# led_matrix.net
KiCad netlist of a schematic drawn in Altium Designer
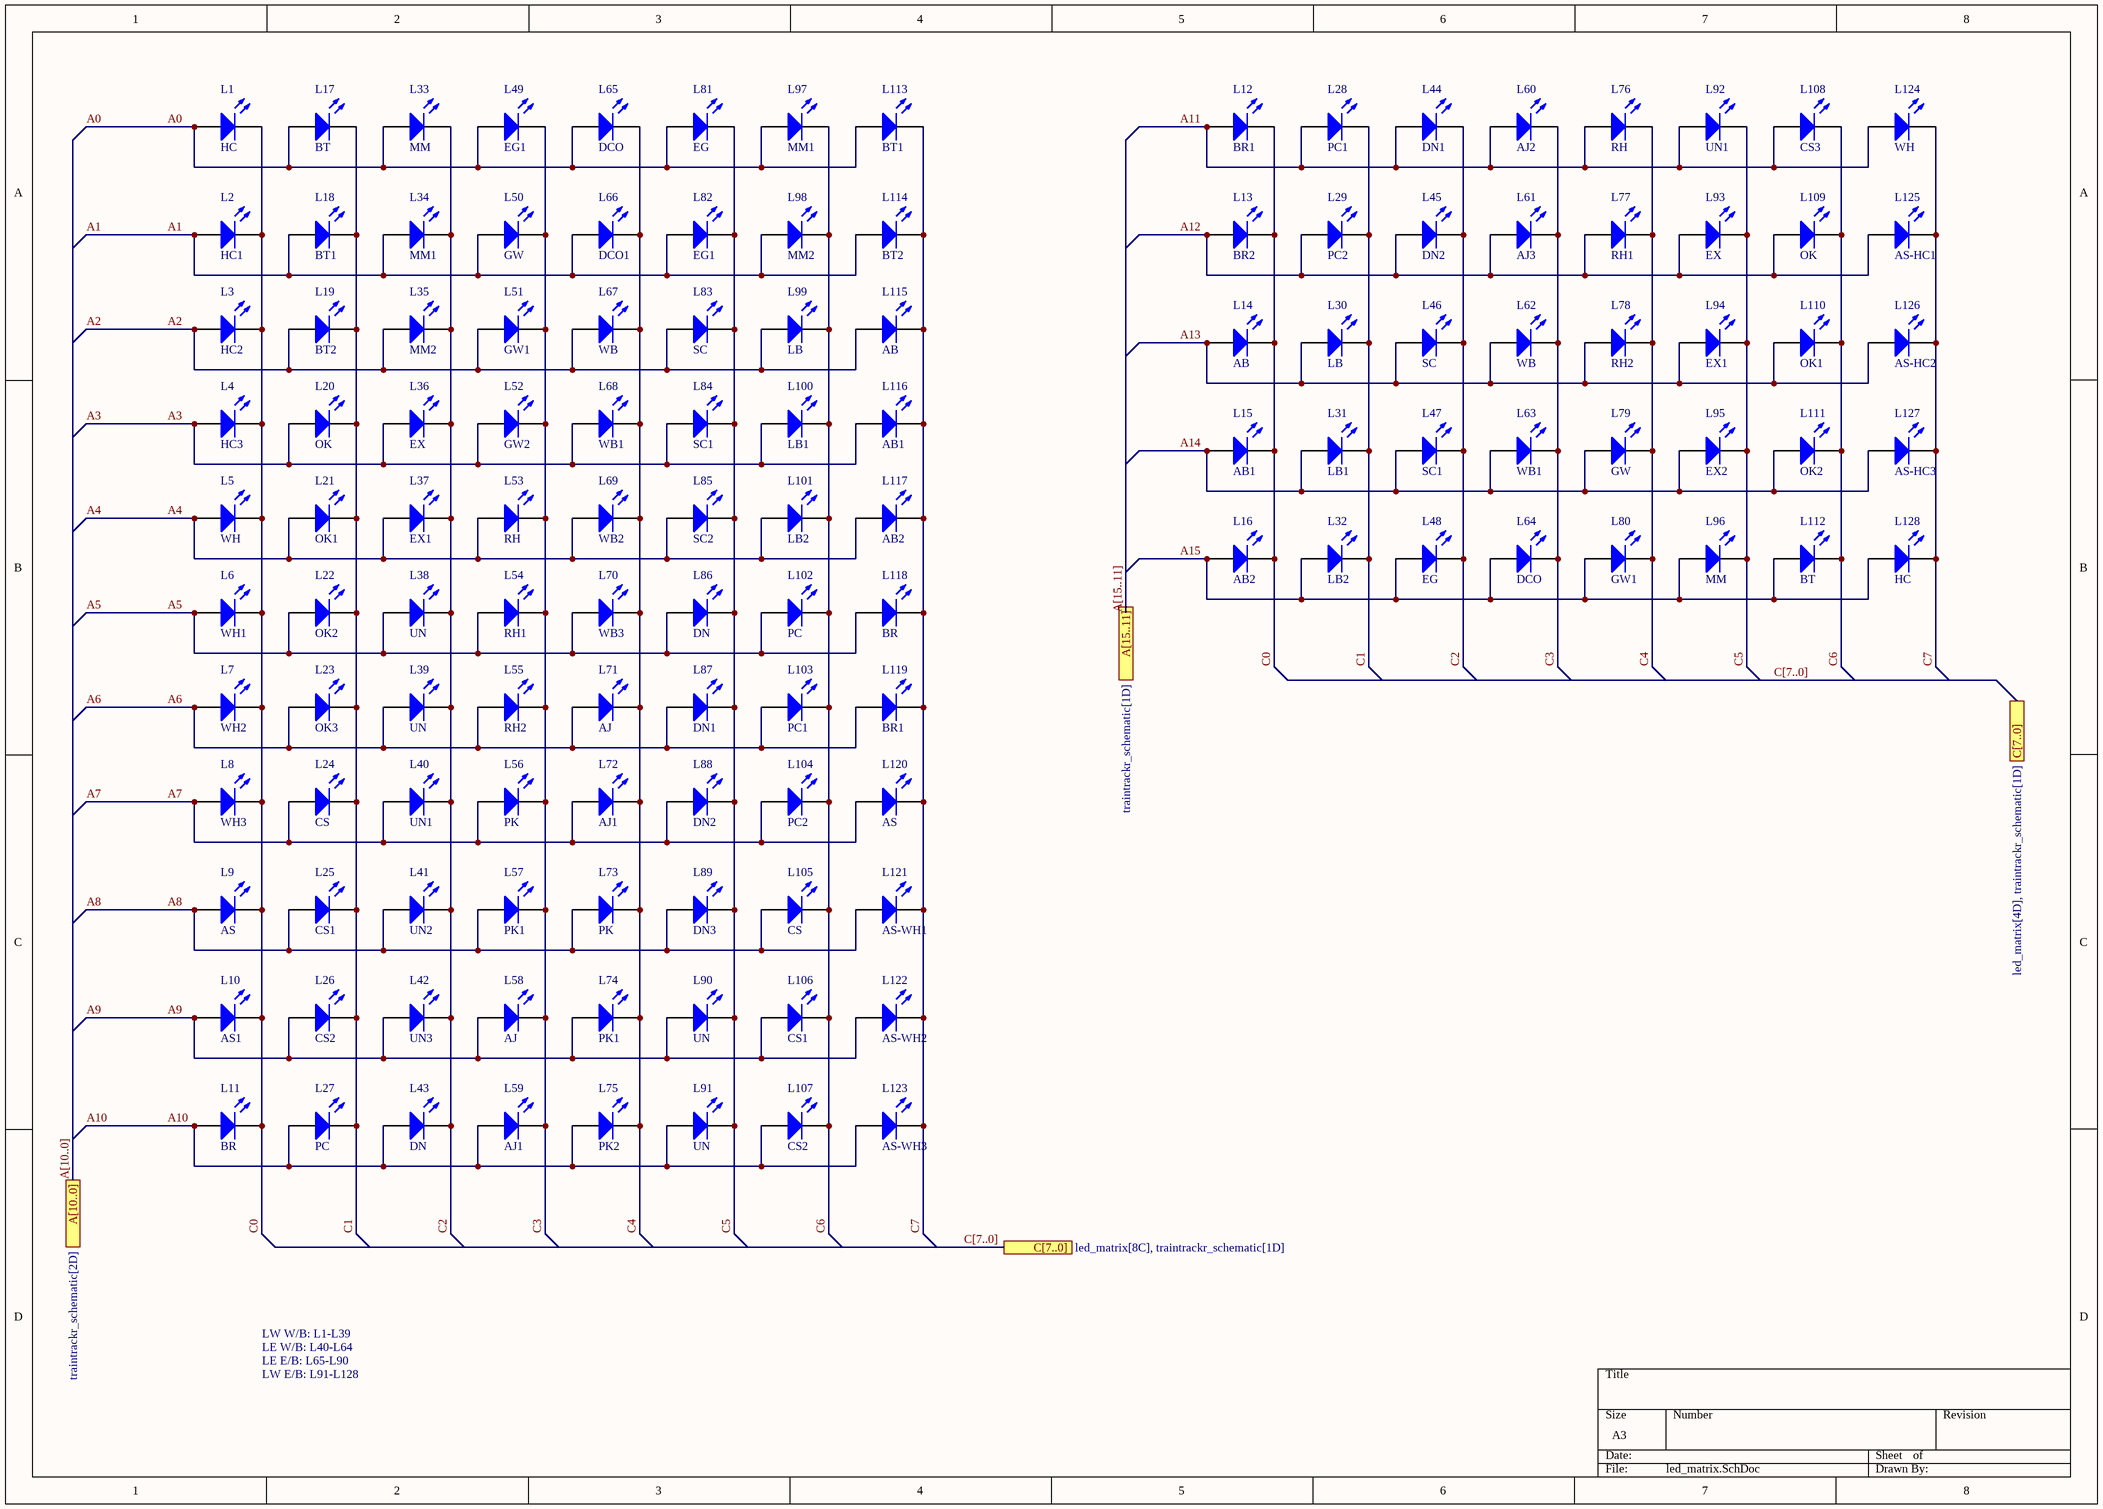
[diagram p0: led_matrix.SchDoc]

(export (version "E")
  (design (tool "Eeschema 10.0.6"))
  (components
    (comp (ref "L1")
      (value "HC")
      (footprint "PCBComponent_1")
      (description "Typical RED GaAs LED")
      (fields (field (name "PUBLISHER") "Altium Limited"))
      (libsource (lib "Miscellaneous Devices") (part "LED1"))
    )
    (comp (ref "L2")
      (value "HC1")
      (footprint "PCBComponent_1")
      (description "Typical RED GaAs LED")
      (fields (field (name "PUBLISHER") "Altium Limited"))
      (libsource (lib "Miscellaneous Devices") (part "LED1"))
    )
    (comp (ref "L3")
      (value "HC2")
      (footprint "PCBComponent_1")
      (description "Typical RED GaAs LED")
      (fields (field (name "PUBLISHER") "Altium Limited"))
      (libsource (lib "Miscellaneous Devices") (part "LED1"))
    )
    (comp (ref "L4")
      (value "HC3")
      (footprint "PCBComponent_1")
      (description "Typical RED GaAs LED")
      (fields (field (name "PUBLISHER") "Altium Limited"))
      (libsource (lib "Miscellaneous Devices") (part "LED1"))
    )
    (comp (ref "L5")
      (value "WH")
      (footprint "PCBComponent_1")
      (description "Typical RED GaAs LED")
      (fields (field (name "PUBLISHER") "Altium Limited"))
      (libsource (lib "Miscellaneous Devices") (part "LED1"))
    )
    (comp (ref "L6")
      (value "WH1")
      (footprint "PCBComponent_1")
      (description "Typical RED GaAs LED")
      (fields (field (name "PUBLISHER") "Altium Limited"))
      (libsource (lib "Miscellaneous Devices") (part "LED1"))
    )
    (comp (ref "L7")
      (value "WH2")
      (footprint "PCBComponent_1")
      (description "Typical RED GaAs LED")
      (fields (field (name "PUBLISHER") "Altium Limited"))
      (libsource (lib "Miscellaneous Devices") (part "LED1"))
    )
    (comp (ref "L8")
      (value "WH3")
      (footprint "PCBComponent_1")
      (description "Typical RED GaAs LED")
      (fields (field (name "PUBLISHER") "Altium Limited"))
      (libsource (lib "Miscellaneous Devices") (part "LED1"))
    )
    (comp (ref "L9")
      (value "AS")
      (footprint "PCBComponent_1")
      (description "Typical RED GaAs LED")
      (fields (field (name "PUBLISHER") "Altium Limited"))
      (libsource (lib "Miscellaneous Devices") (part "LED1"))
    )
    (comp (ref "L10")
      (value "AS1")
      (footprint "PCBComponent_1")
      (description "Typical RED GaAs LED")
      (fields (field (name "PUBLISHER") "Altium Limited"))
      (libsource (lib "Miscellaneous Devices") (part "LED1"))
    )
    (comp (ref "L11")
      (value "BR")
      (footprint "PCBComponent_1")
      (description "Typical RED GaAs LED")
      (fields (field (name "PUBLISHER") "Altium Limited"))
      (libsource (lib "Miscellaneous Devices") (part "LED1"))
    )
    (comp (ref "L12")
      (value "BR1")
      (footprint "PCBComponent_1")
      (description "Typical RED GaAs LED")
      (fields (field (name "PUBLISHER") "Altium Limited"))
      (libsource (lib "Miscellaneous Devices") (part "LED1"))
    )
    (comp (ref "L13")
      (value "BR2")
      (footprint "PCBComponent_1")
      (description "Typical RED GaAs LED")
      (fields (field (name "PUBLISHER") "Altium Limited"))
      (libsource (lib "Miscellaneous Devices") (part "LED1"))
    )
    (comp (ref "L14")
      (value "AB")
      (footprint "PCBComponent_1")
      (description "Typical RED GaAs LED")
      (fields (field (name "PUBLISHER") "Altium Limited"))
      (libsource (lib "Miscellaneous Devices") (part "LED1"))
    )
    (comp (ref "L15")
      (value "AB1")
      (footprint "PCBComponent_1")
      (description "Typical RED GaAs LED")
      (fields (field (name "PUBLISHER") "Altium Limited"))
      (libsource (lib "Miscellaneous Devices") (part "LED1"))
    )
    (comp (ref "L16")
      (value "AB2")
      (footprint "PCBComponent_1")
      (description "Typical RED GaAs LED")
      (fields (field (name "PUBLISHER") "Altium Limited"))
      (libsource (lib "Miscellaneous Devices") (part "LED1"))
    )
    (comp (ref "L17")
      (value "BT")
      (footprint "PCBComponent_1")
      (description "Typical RED GaAs LED")
      (fields (field (name "PUBLISHER") "Altium Limited"))
      (libsource (lib "Miscellaneous Devices") (part "LED1"))
    )
    (comp (ref "L18")
      (value "BT1")
      (footprint "PCBComponent_1")
      (description "Typical RED GaAs LED")
      (fields (field (name "PUBLISHER") "Altium Limited"))
      (libsource (lib "Miscellaneous Devices") (part "LED1"))
    )
    (comp (ref "L19")
      (value "BT2")
      (footprint "PCBComponent_1")
      (description "Typical RED GaAs LED")
      (fields (field (name "PUBLISHER") "Altium Limited"))
      (libsource (lib "Miscellaneous Devices") (part "LED1"))
    )
    (comp (ref "L20")
      (value "OK")
      (footprint "PCBComponent_1")
      (description "Typical RED GaAs LED")
      (fields (field (name "PUBLISHER") "Altium Limited"))
      (libsource (lib "Miscellaneous Devices") (part "LED1"))
    )
    (comp (ref "L21")
      (value "OK1")
      (footprint "PCBComponent_1")
      (description "Typical RED GaAs LED")
      (fields (field (name "PUBLISHER") "Altium Limited"))
      (libsource (lib "Miscellaneous Devices") (part "LED1"))
    )
    (comp (ref "L22")
      (value "OK2")
      (footprint "PCBComponent_1")
      (description "Typical RED GaAs LED")
      (fields (field (name "PUBLISHER") "Altium Limited"))
      (libsource (lib "Miscellaneous Devices") (part "LED1"))
    )
    (comp (ref "L23")
      (value "OK3")
      (footprint "PCBComponent_1")
      (description "Typical RED GaAs LED")
      (fields (field (name "PUBLISHER") "Altium Limited"))
      (libsource (lib "Miscellaneous Devices") (part "LED1"))
    )
    (comp (ref "L24")
      (value "CS")
      (footprint "PCBComponent_1")
      (description "Typical RED GaAs LED")
      (fields (field (name "PUBLISHER") "Altium Limited"))
      (libsource (lib "Miscellaneous Devices") (part "LED1"))
    )
    (comp (ref "L25")
      (value "CS1")
      (footprint "PCBComponent_1")
      (description "Typical RED GaAs LED")
      (fields (field (name "PUBLISHER") "Altium Limited"))
      (libsource (lib "Miscellaneous Devices") (part "LED1"))
    )
    (comp (ref "L26")
      (value "CS2")
      (footprint "PCBComponent_1")
      (description "Typical RED GaAs LED")
      (fields (field (name "PUBLISHER") "Altium Limited"))
      (libsource (lib "Miscellaneous Devices") (part "LED1"))
    )
    (comp (ref "L27")
      (value "PC")
      (footprint "PCBComponent_1")
      (description "Typical RED GaAs LED")
      (fields (field (name "PUBLISHER") "Altium Limited"))
      (libsource (lib "Miscellaneous Devices") (part "LED1"))
    )
    (comp (ref "L28")
      (value "PC1")
      (footprint "PCBComponent_1")
      (description "Typical RED GaAs LED")
      (fields (field (name "PUBLISHER") "Altium Limited"))
      (libsource (lib "Miscellaneous Devices") (part "LED1"))
    )
    (comp (ref "L29")
      (value "PC2")
      (footprint "PCBComponent_1")
      (description "Typical RED GaAs LED")
      (fields (field (name "PUBLISHER") "Altium Limited"))
      (libsource (lib "Miscellaneous Devices") (part "LED1"))
    )
    (comp (ref "L30")
      (value "LB")
      (footprint "PCBComponent_1")
      (description "Typical RED GaAs LED")
      (fields (field (name "PUBLISHER") "Altium Limited"))
      (libsource (lib "Miscellaneous Devices") (part "LED1"))
    )
    (comp (ref "L31")
      (value "LB1")
      (footprint "PCBComponent_1")
      (description "Typical RED GaAs LED")
      (fields (field (name "PUBLISHER") "Altium Limited"))
      (libsource (lib "Miscellaneous Devices") (part "LED1"))
    )
    (comp (ref "L32")
      (value "LB2")
      (footprint "PCBComponent_1")
      (description "Typical RED GaAs LED")
      (fields (field (name "PUBLISHER") "Altium Limited"))
      (libsource (lib "Miscellaneous Devices") (part "LED1"))
    )
    (comp (ref "L33")
      (value "MM")
      (footprint "PCBComponent_1")
      (description "Typical RED GaAs LED")
      (fields (field (name "PUBLISHER") "Altium Limited"))
      (libsource (lib "Miscellaneous Devices") (part "LED1"))
    )
    (comp (ref "L34")
      (value "MM1")
      (footprint "PCBComponent_1")
      (description "Typical RED GaAs LED")
      (fields (field (name "PUBLISHER") "Altium Limited"))
      (libsource (lib "Miscellaneous Devices") (part "LED1"))
    )
    (comp (ref "L35")
      (value "MM2")
      (footprint "PCBComponent_1")
      (description "Typical RED GaAs LED")
      (fields (field (name "PUBLISHER") "Altium Limited"))
      (libsource (lib "Miscellaneous Devices") (part "LED1"))
    )
    (comp (ref "L36")
      (value "EX")
      (footprint "PCBComponent_1")
      (description "Typical RED GaAs LED")
      (fields (field (name "PUBLISHER") "Altium Limited"))
      (libsource (lib "Miscellaneous Devices") (part "LED1"))
    )
    (comp (ref "L37")
      (value "EX1")
      (footprint "PCBComponent_1")
      (description "Typical RED GaAs LED")
      (fields (field (name "PUBLISHER") "Altium Limited"))
      (libsource (lib "Miscellaneous Devices") (part "LED1"))
    )
    (comp (ref "L38")
      (value "UN")
      (footprint "PCBComponent_1")
      (description "Typical RED GaAs LED")
      (fields (field (name "PUBLISHER") "Altium Limited"))
      (libsource (lib "Miscellaneous Devices") (part "LED1"))
    )
    (comp (ref "L39")
      (value "UN")
      (footprint "PCBComponent_1")
      (description "Typical RED GaAs LED")
      (fields (field (name "PUBLISHER") "Altium Limited"))
      (libsource (lib "Miscellaneous Devices") (part "LED1"))
    )
    (comp (ref "L40")
      (value "UN1")
      (footprint "PCBComponent_1")
      (description "Typical RED GaAs LED")
      (fields (field (name "PUBLISHER") "Altium Limited"))
      (libsource (lib "Miscellaneous Devices") (part "LED1"))
    )
    (comp (ref "L41")
      (value "UN2")
      (footprint "PCBComponent_1")
      (description "Typical RED GaAs LED")
      (fields (field (name "PUBLISHER") "Altium Limited"))
      (libsource (lib "Miscellaneous Devices") (part "LED1"))
    )
    (comp (ref "L42")
      (value "UN3")
      (footprint "PCBComponent_1")
      (description "Typical RED GaAs LED")
      (fields (field (name "PUBLISHER") "Altium Limited"))
      (libsource (lib "Miscellaneous Devices") (part "LED1"))
    )
    (comp (ref "L43")
      (value "DN")
      (footprint "PCBComponent_1")
      (description "Typical RED GaAs LED")
      (fields (field (name "PUBLISHER") "Altium Limited"))
      (libsource (lib "Miscellaneous Devices") (part "LED1"))
    )
    (comp (ref "L44")
      (value "DN1")
      (footprint "PCBComponent_1")
      (description "Typical RED GaAs LED")
      (fields (field (name "PUBLISHER") "Altium Limited"))
      (libsource (lib "Miscellaneous Devices") (part "LED1"))
    )
    (comp (ref "L45")
      (value "DN2")
      (footprint "PCBComponent_1")
      (description "Typical RED GaAs LED")
      (fields (field (name "PUBLISHER") "Altium Limited"))
      (libsource (lib "Miscellaneous Devices") (part "LED1"))
    )
    (comp (ref "L46")
      (value "SC")
      (footprint "PCBComponent_1")
      (description "Typical RED GaAs LED")
      (fields (field (name "PUBLISHER") "Altium Limited"))
      (libsource (lib "Miscellaneous Devices") (part "LED1"))
    )
    (comp (ref "L47")
      (value "SC1")
      (footprint "PCBComponent_1")
      (description "Typical RED GaAs LED")
      (fields (field (name "PUBLISHER") "Altium Limited"))
      (libsource (lib "Miscellaneous Devices") (part "LED1"))
    )
    (comp (ref "L48")
      (value "EG")
      (footprint "PCBComponent_1")
      (description "Typical RED GaAs LED")
      (fields (field (name "PUBLISHER") "Altium Limited"))
      (libsource (lib "Miscellaneous Devices") (part "LED1"))
    )
    (comp (ref "L49")
      (value "EG1")
      (footprint "PCBComponent_1")
      (description "Typical RED GaAs LED")
      (fields (field (name "PUBLISHER") "Altium Limited"))
      (libsource (lib "Miscellaneous Devices") (part "LED1"))
    )
    (comp (ref "L50")
      (value "GW")
      (footprint "PCBComponent_1")
      (description "Typical RED GaAs LED")
      (fields (field (name "PUBLISHER") "Altium Limited"))
      (libsource (lib "Miscellaneous Devices") (part "LED1"))
    )
    (comp (ref "L51")
      (value "GW1")
      (footprint "PCBComponent_1")
      (description "Typical RED GaAs LED")
      (fields (field (name "PUBLISHER") "Altium Limited"))
      (libsource (lib "Miscellaneous Devices") (part "LED1"))
    )
    (comp (ref "L52")
      (value "GW2")
      (footprint "PCBComponent_1")
      (description "Typical RED GaAs LED")
      (fields (field (name "PUBLISHER") "Altium Limited"))
      (libsource (lib "Miscellaneous Devices") (part "LED1"))
    )
    (comp (ref "L53")
      (value "RH")
      (footprint "PCBComponent_1")
      (description "Typical RED GaAs LED")
      (fields (field (name "PUBLISHER") "Altium Limited"))
      (libsource (lib "Miscellaneous Devices") (part "LED1"))
    )
    (comp (ref "L54")
      (value "RH1")
      (footprint "PCBComponent_1")
      (description "Typical RED GaAs LED")
      (fields (field (name "PUBLISHER") "Altium Limited"))
      (libsource (lib "Miscellaneous Devices") (part "LED1"))
    )
    (comp (ref "L55")
      (value "RH2")
      (footprint "PCBComponent_1")
      (description "Typical RED GaAs LED")
      (fields (field (name "PUBLISHER") "Altium Limited"))
      (libsource (lib "Miscellaneous Devices") (part "LED1"))
    )
    (comp (ref "L56")
      (value "PK")
      (footprint "PCBComponent_1")
      (description "Typical RED GaAs LED")
      (fields (field (name "PUBLISHER") "Altium Limited"))
      (libsource (lib "Miscellaneous Devices") (part "LED1"))
    )
    (comp (ref "L57")
      (value "PK1")
      (footprint "PCBComponent_1")
      (description "Typical RED GaAs LED")
      (fields (field (name "PUBLISHER") "Altium Limited"))
      (libsource (lib "Miscellaneous Devices") (part "LED1"))
    )
    (comp (ref "L58")
      (value "AJ")
      (footprint "PCBComponent_1")
      (description "Typical RED GaAs LED")
      (fields (field (name "PUBLISHER") "Altium Limited"))
      (libsource (lib "Miscellaneous Devices") (part "LED1"))
    )
    (comp (ref "L59")
      (value "AJ1")
      (footprint "PCBComponent_1")
      (description "Typical RED GaAs LED")
      (fields (field (name "PUBLISHER") "Altium Limited"))
      (libsource (lib "Miscellaneous Devices") (part "LED1"))
    )
    (comp (ref "L60")
      (value "AJ2")
      (footprint "PCBComponent_1")
      (description "Typical RED GaAs LED")
      (fields (field (name "PUBLISHER") "Altium Limited"))
      (libsource (lib "Miscellaneous Devices") (part "LED1"))
    )
    (comp (ref "L61")
      (value "AJ3")
      (footprint "PCBComponent_1")
      (description "Typical RED GaAs LED")
      (fields (field (name "PUBLISHER") "Altium Limited"))
      (libsource (lib "Miscellaneous Devices") (part "LED1"))
    )
    (comp (ref "L62")
      (value "WB")
      (footprint "PCBComponent_1")
      (description "Typical RED GaAs LED")
      (fields (field (name "PUBLISHER") "Altium Limited"))
      (libsource (lib "Miscellaneous Devices") (part "LED1"))
    )
    (comp (ref "L63")
      (value "WB1")
      (footprint "PCBComponent_1")
      (description "Typical RED GaAs LED")
      (fields (field (name "PUBLISHER") "Altium Limited"))
      (libsource (lib "Miscellaneous Devices") (part "LED1"))
    )
    (comp (ref "L64")
      (value "DCO")
      (footprint "PCBComponent_1")
      (description "Typical RED GaAs LED")
      (fields (field (name "PUBLISHER") "Altium Limited"))
      (libsource (lib "Miscellaneous Devices") (part "LED1"))
    )
    (comp (ref "L65")
      (value "DCO")
      (footprint "PCBComponent_1")
      (description "Typical RED GaAs LED")
      (fields (field (name "PUBLISHER") "Altium Limited"))
      (libsource (lib "Miscellaneous Devices") (part "LED1"))
    )
    (comp (ref "L66")
      (value "DCO1")
      (footprint "PCBComponent_1")
      (description "Typical RED GaAs LED")
      (fields (field (name "PUBLISHER") "Altium Limited"))
      (libsource (lib "Miscellaneous Devices") (part "LED1"))
    )
    (comp (ref "L67")
      (value "WB")
      (footprint "PCBComponent_1")
      (description "Typical RED GaAs LED")
      (fields (field (name "PUBLISHER") "Altium Limited"))
      (libsource (lib "Miscellaneous Devices") (part "LED1"))
    )
    (comp (ref "L68")
      (value "WB1")
      (footprint "PCBComponent_1")
      (description "Typical RED GaAs LED")
      (fields (field (name "PUBLISHER") "Altium Limited"))
      (libsource (lib "Miscellaneous Devices") (part "LED1"))
    )
    (comp (ref "L69")
      (value "WB2")
      (footprint "PCBComponent_1")
      (description "Typical RED GaAs LED")
      (fields (field (name "PUBLISHER") "Altium Limited"))
      (libsource (lib "Miscellaneous Devices") (part "LED1"))
    )
    (comp (ref "L70")
      (value "WB3")
      (footprint "PCBComponent_1")
      (description "Typical RED GaAs LED")
      (fields (field (name "PUBLISHER") "Altium Limited"))
      (libsource (lib "Miscellaneous Devices") (part "LED1"))
    )
    (comp (ref "L71")
      (value "AJ")
      (footprint "PCBComponent_1")
      (description "Typical RED GaAs LED")
      (fields (field (name "PUBLISHER") "Altium Limited"))
      (libsource (lib "Miscellaneous Devices") (part "LED1"))
    )
    (comp (ref "L72")
      (value "AJ1")
      (footprint "PCBComponent_1")
      (description "Typical RED GaAs LED")
      (fields (field (name "PUBLISHER") "Altium Limited"))
      (libsource (lib "Miscellaneous Devices") (part "LED1"))
    )
    (comp (ref "L73")
      (value "PK")
      (footprint "PCBComponent_1")
      (description "Typical RED GaAs LED")
      (fields (field (name "PUBLISHER") "Altium Limited"))
      (libsource (lib "Miscellaneous Devices") (part "LED1"))
    )
    (comp (ref "L74")
      (value "PK1")
      (footprint "PCBComponent_1")
      (description "Typical RED GaAs LED")
      (fields (field (name "PUBLISHER") "Altium Limited"))
      (libsource (lib "Miscellaneous Devices") (part "LED1"))
    )
    (comp (ref "L75")
      (value "PK2")
      (footprint "PCBComponent_1")
      (description "Typical RED GaAs LED")
      (fields (field (name "PUBLISHER") "Altium Limited"))
      (libsource (lib "Miscellaneous Devices") (part "LED1"))
    )
    (comp (ref "L76")
      (value "RH")
      (footprint "PCBComponent_1")
      (description "Typical RED GaAs LED")
      (fields (field (name "PUBLISHER") "Altium Limited"))
      (libsource (lib "Miscellaneous Devices") (part "LED1"))
    )
    (comp (ref "L77")
      (value "RH1")
      (footprint "PCBComponent_1")
      (description "Typical RED GaAs LED")
      (fields (field (name "PUBLISHER") "Altium Limited"))
      (libsource (lib "Miscellaneous Devices") (part "LED1"))
    )
    (comp (ref "L78")
      (value "RH2")
      (footprint "PCBComponent_1")
      (description "Typical RED GaAs LED")
      (fields (field (name "PUBLISHER") "Altium Limited"))
      (libsource (lib "Miscellaneous Devices") (part "LED1"))
    )
    (comp (ref "L79")
      (value "GW")
      (footprint "PCBComponent_1")
      (description "Typical RED GaAs LED")
      (fields (field (name "PUBLISHER") "Altium Limited"))
      (libsource (lib "Miscellaneous Devices") (part "LED1"))
    )
    (comp (ref "L80")
      (value "GW1")
      (footprint "PCBComponent_1")
      (description "Typical RED GaAs LED")
      (fields (field (name "PUBLISHER") "Altium Limited"))
      (libsource (lib "Miscellaneous Devices") (part "LED1"))
    )
    (comp (ref "L81")
      (value "EG")
      (footprint "PCBComponent_1")
      (description "Typical RED GaAs LED")
      (fields (field (name "PUBLISHER") "Altium Limited"))
      (libsource (lib "Miscellaneous Devices") (part "LED1"))
    )
    (comp (ref "L82")
      (value "EG1")
      (footprint "PCBComponent_1")
      (description "Typical RED GaAs LED")
      (fields (field (name "PUBLISHER") "Altium Limited"))
      (libsource (lib "Miscellaneous Devices") (part "LED1"))
    )
    (comp (ref "L83")
      (value "SC")
      (footprint "PCBComponent_1")
      (description "Typical RED GaAs LED")
      (fields (field (name "PUBLISHER") "Altium Limited"))
      (libsource (lib "Miscellaneous Devices") (part "LED1"))
    )
    (comp (ref "L84")
      (value "SC1")
      (footprint "PCBComponent_1")
      (description "Typical RED GaAs LED")
      (fields (field (name "PUBLISHER") "Altium Limited"))
      (libsource (lib "Miscellaneous Devices") (part "LED1"))
    )
    (comp (ref "L85")
      (value "SC2")
      (footprint "PCBComponent_1")
      (description "Typical RED GaAs LED")
      (fields (field (name "PUBLISHER") "Altium Limited"))
      (libsource (lib "Miscellaneous Devices") (part "LED1"))
    )
    (comp (ref "L86")
      (value "DN")
      (footprint "PCBComponent_1")
      (description "Typical RED GaAs LED")
      (fields (field (name "PUBLISHER") "Altium Limited"))
      (libsource (lib "Miscellaneous Devices") (part "LED1"))
    )
    (comp (ref "L87")
      (value "DN1")
      (footprint "PCBComponent_1")
      (description "Typical RED GaAs LED")
      (fields (field (name "PUBLISHER") "Altium Limited"))
      (libsource (lib "Miscellaneous Devices") (part "LED1"))
    )
    (comp (ref "L88")
      (value "DN2")
      (footprint "PCBComponent_1")
      (description "Typical RED GaAs LED")
      (fields (field (name "PUBLISHER") "Altium Limited"))
      (libsource (lib "Miscellaneous Devices") (part "LED1"))
    )
    (comp (ref "L89")
      (value "DN3")
      (footprint "PCBComponent_1")
      (description "Typical RED GaAs LED")
      (fields (field (name "PUBLISHER") "Altium Limited"))
      (libsource (lib "Miscellaneous Devices") (part "LED1"))
    )
    (comp (ref "L90")
      (value "UN")
      (footprint "PCBComponent_1")
      (description "Typical RED GaAs LED")
      (fields (field (name "PUBLISHER") "Altium Limited"))
      (libsource (lib "Miscellaneous Devices") (part "LED1"))
    )
    (comp (ref "L91")
      (value "UN")
      (footprint "PCBComponent_1")
      (description "Typical RED GaAs LED")
      (fields (field (name "PUBLISHER") "Altium Limited"))
      (libsource (lib "Miscellaneous Devices") (part "LED1"))
    )
    (comp (ref "L92")
      (value "UN1")
      (footprint "PCBComponent_1")
      (description "Typical RED GaAs LED")
      (fields (field (name "PUBLISHER") "Altium Limited"))
      (libsource (lib "Miscellaneous Devices") (part "LED1"))
    )
    (comp (ref "L93")
      (value "EX")
      (footprint "PCBComponent_1")
      (description "Typical RED GaAs LED")
      (fields (field (name "PUBLISHER") "Altium Limited"))
      (libsource (lib "Miscellaneous Devices") (part "LED1"))
    )
    (comp (ref "L94")
      (value "EX1")
      (footprint "PCBComponent_1")
      (description "Typical RED GaAs LED")
      (fields (field (name "PUBLISHER") "Altium Limited"))
      (libsource (lib "Miscellaneous Devices") (part "LED1"))
    )
    (comp (ref "L95")
      (value "EX2")
      (footprint "PCBComponent_1")
      (description "Typical RED GaAs LED")
      (fields (field (name "PUBLISHER") "Altium Limited"))
      (libsource (lib "Miscellaneous Devices") (part "LED1"))
    )
    (comp (ref "L96")
      (value "MM")
      (footprint "PCBComponent_1")
      (description "Typical RED GaAs LED")
      (fields (field (name "PUBLISHER") "Altium Limited"))
      (libsource (lib "Miscellaneous Devices") (part "LED1"))
    )
    (comp (ref "L97")
      (value "MM1")
      (footprint "PCBComponent_1")
      (description "Typical RED GaAs LED")
      (fields (field (name "PUBLISHER") "Altium Limited"))
      (libsource (lib "Miscellaneous Devices") (part "LED1"))
    )
    (comp (ref "L98")
      (value "MM2")
      (footprint "PCBComponent_1")
      (description "Typical RED GaAs LED")
      (fields (field (name "PUBLISHER") "Altium Limited"))
      (libsource (lib "Miscellaneous Devices") (part "LED1"))
    )
    (comp (ref "L99")
      (value "LB")
      (footprint "PCBComponent_1")
      (description "Typical RED GaAs LED")
      (fields (field (name "PUBLISHER") "Altium Limited"))
      (libsource (lib "Miscellaneous Devices") (part "LED1"))
    )
    (comp (ref "L100")
      (value "LB1")
      (footprint "PCBComponent_1")
      (description "Typical RED GaAs LED")
      (fields (field (name "PUBLISHER") "Altium Limited"))
      (libsource (lib "Miscellaneous Devices") (part "LED1"))
    )
    (comp (ref "L101")
      (value "LB2")
      (footprint "PCBComponent_1")
      (description "Typical RED GaAs LED")
      (fields (field (name "PUBLISHER") "Altium Limited"))
      (libsource (lib "Miscellaneous Devices") (part "LED1"))
    )
    (comp (ref "L102")
      (value "PC")
      (footprint "PCBComponent_1")
      (description "Typical RED GaAs LED")
      (fields (field (name "PUBLISHER") "Altium Limited"))
      (libsource (lib "Miscellaneous Devices") (part "LED1"))
    )
    (comp (ref "L103")
      (value "PC1")
      (footprint "PCBComponent_1")
      (description "Typical RED GaAs LED")
      (fields (field (name "PUBLISHER") "Altium Limited"))
      (libsource (lib "Miscellaneous Devices") (part "LED1"))
    )
    (comp (ref "L104")
      (value "PC2")
      (footprint "PCBComponent_1")
      (description "Typical RED GaAs LED")
      (fields (field (name "PUBLISHER") "Altium Limited"))
      (libsource (lib "Miscellaneous Devices") (part "LED1"))
    )
    (comp (ref "L105")
      (value "CS")
      (footprint "PCBComponent_1")
      (description "Typical RED GaAs LED")
      (fields (field (name "PUBLISHER") "Altium Limited"))
      (libsource (lib "Miscellaneous Devices") (part "LED1"))
    )
    (comp (ref "L106")
      (value "CS1")
      (footprint "PCBComponent_1")
      (description "Typical RED GaAs LED")
      (fields (field (name "PUBLISHER") "Altium Limited"))
      (libsource (lib "Miscellaneous Devices") (part "LED1"))
    )
    (comp (ref "L107")
      (value "CS2")
      (footprint "PCBComponent_1")
      (description "Typical RED GaAs LED")
      (fields (field (name "PUBLISHER") "Altium Limited"))
      (libsource (lib "Miscellaneous Devices") (part "LED1"))
    )
    (comp (ref "L108")
      (value "CS3")
      (footprint "PCBComponent_1")
      (description "Typical RED GaAs LED")
      (fields (field (name "PUBLISHER") "Altium Limited"))
      (libsource (lib "Miscellaneous Devices") (part "LED1"))
    )
    (comp (ref "L109")
      (value "OK")
      (footprint "PCBComponent_1")
      (description "Typical RED GaAs LED")
      (fields (field (name "PUBLISHER") "Altium Limited"))
      (libsource (lib "Miscellaneous Devices") (part "LED1"))
    )
    (comp (ref "L110")
      (value "OK1")
      (footprint "PCBComponent_1")
      (description "Typical RED GaAs LED")
      (fields (field (name "PUBLISHER") "Altium Limited"))
      (libsource (lib "Miscellaneous Devices") (part "LED1"))
    )
    (comp (ref "L111")
      (value "OK2")
      (footprint "PCBComponent_1")
      (description "Typical RED GaAs LED")
      (fields (field (name "PUBLISHER") "Altium Limited"))
      (libsource (lib "Miscellaneous Devices") (part "LED1"))
    )
    (comp (ref "L112")
      (value "BT")
      (footprint "PCBComponent_1")
      (description "Typical RED GaAs LED")
      (fields (field (name "PUBLISHER") "Altium Limited"))
      (libsource (lib "Miscellaneous Devices") (part "LED1"))
    )
    (comp (ref "L113")
      (value "BT1")
      (footprint "PCBComponent_1")
      (description "Typical RED GaAs LED")
      (fields (field (name "PUBLISHER") "Altium Limited"))
      (libsource (lib "Miscellaneous Devices") (part "LED1"))
    )
    (comp (ref "L114")
      (value "BT2")
      (footprint "PCBComponent_1")
      (description "Typical RED GaAs LED")
      (fields (field (name "PUBLISHER") "Altium Limited"))
      (libsource (lib "Miscellaneous Devices") (part "LED1"))
    )
    (comp (ref "L115")
      (value "AB")
      (footprint "PCBComponent_1")
      (description "Typical RED GaAs LED")
      (fields (field (name "PUBLISHER") "Altium Limited"))
      (libsource (lib "Miscellaneous Devices") (part "LED1"))
    )
    (comp (ref "L116")
      (value "AB1")
      (footprint "PCBComponent_1")
      (description "Typical RED GaAs LED")
      (fields (field (name "PUBLISHER") "Altium Limited"))
      (libsource (lib "Miscellaneous Devices") (part "LED1"))
    )
    (comp (ref "L117")
      (value "AB2")
      (footprint "PCBComponent_1")
      (description "Typical RED GaAs LED")
      (fields (field (name "PUBLISHER") "Altium Limited"))
      (libsource (lib "Miscellaneous Devices") (part "LED1"))
    )
    (comp (ref "L118")
      (value "BR")
      (footprint "PCBComponent_1")
      (description "Typical RED GaAs LED")
      (fields (field (name "PUBLISHER") "Altium Limited"))
      (libsource (lib "Miscellaneous Devices") (part "LED1"))
    )
    (comp (ref "L119")
      (value "BR1")
      (footprint "PCBComponent_1")
      (description "Typical RED GaAs LED")
      (fields (field (name "PUBLISHER") "Altium Limited"))
      (libsource (lib "Miscellaneous Devices") (part "LED1"))
    )
    (comp (ref "L120")
      (value "AS")
      (footprint "PCBComponent_1")
      (description "Typical RED GaAs LED")
      (fields (field (name "PUBLISHER") "Altium Limited"))
      (libsource (lib "Miscellaneous Devices") (part "LED1"))
    )
    (comp (ref "L121")
      (value "AS-WH1")
      (footprint "PCBComponent_1")
      (description "Typical RED GaAs LED")
      (fields (field (name "PUBLISHER") "Altium Limited"))
      (libsource (lib "Miscellaneous Devices") (part "LED1"))
    )
    (comp (ref "L122")
      (value "AS-WH2")
      (footprint "PCBComponent_1")
      (description "Typical RED GaAs LED")
      (fields (field (name "PUBLISHER") "Altium Limited"))
      (libsource (lib "Miscellaneous Devices") (part "LED1"))
    )
    (comp (ref "L123")
      (value "AS-WH3")
      (footprint "PCBComponent_1")
      (description "Typical RED GaAs LED")
      (fields (field (name "PUBLISHER") "Altium Limited"))
      (libsource (lib "Miscellaneous Devices") (part "LED1"))
    )
    (comp (ref "L124")
      (value "WH")
      (footprint "PCBComponent_1")
      (description "Typical RED GaAs LED")
      (fields (field (name "PUBLISHER") "Altium Limited"))
      (libsource (lib "Miscellaneous Devices") (part "LED1"))
    )
    (comp (ref "L125")
      (value "AS-HC1")
      (footprint "PCBComponent_1")
      (description "Typical RED GaAs LED")
      (fields (field (name "PUBLISHER") "Altium Limited"))
      (libsource (lib "Miscellaneous Devices") (part "LED1"))
    )
    (comp (ref "L126")
      (value "AS-HC2")
      (footprint "PCBComponent_1")
      (description "Typical RED GaAs LED")
      (fields (field (name "PUBLISHER") "Altium Limited"))
      (libsource (lib "Miscellaneous Devices") (part "LED1"))
    )
    (comp (ref "L127")
      (value "AS-HC3")
      (footprint "PCBComponent_1")
      (description "Typical RED GaAs LED")
      (fields (field (name "PUBLISHER") "Altium Limited"))
      (libsource (lib "Miscellaneous Devices") (part "LED1"))
    )
    (comp (ref "L128")
      (value "HC")
      (footprint "PCBComponent_1")
      (description "Typical RED GaAs LED")
      (fields (field (name "PUBLISHER") "Altium Limited"))
      (libsource (lib "Miscellaneous Devices") (part "LED1"))
    )
  )
  (nets
    (net (code "1") (name "/A0") (class "Default")
      (node (ref "L1") (pin "1") (pinfunction "A_1") (pintype "passive"))
      (node (ref "L113") (pin "1") (pinfunction "A_1") (pintype "passive"))
      (node (ref "L17") (pin "1") (pinfunction "A_1") (pintype "passive"))
      (node (ref "L33") (pin "1") (pinfunction "A_1") (pintype "passive"))
      (node (ref "L49") (pin "1") (pinfunction "A_1") (pintype "passive"))
      (node (ref "L65") (pin "1") (pinfunction "A_1") (pintype "passive"))
      (node (ref "L81") (pin "1") (pinfunction "A_1") (pintype "passive"))
      (node (ref "L97") (pin "1") (pinfunction "A_1") (pintype "passive"))
    )
    (net (code "2") (name "/A1") (class "Default")
      (node (ref "L114") (pin "1") (pinfunction "A_1") (pintype "passive"))
      (node (ref "L18") (pin "1") (pinfunction "A_1") (pintype "passive"))
      (node (ref "L2") (pin "1") (pinfunction "A_1") (pintype "passive"))
      (node (ref "L34") (pin "1") (pinfunction "A_1") (pintype "passive"))
      (node (ref "L50") (pin "1") (pinfunction "A_1") (pintype "passive"))
      (node (ref "L66") (pin "1") (pinfunction "A_1") (pintype "passive"))
      (node (ref "L82") (pin "1") (pinfunction "A_1") (pintype "passive"))
      (node (ref "L98") (pin "1") (pinfunction "A_1") (pintype "passive"))
    )
    (net (code "3") (name "/A2") (class "Default")
      (node (ref "L115") (pin "1") (pinfunction "A_1") (pintype "passive"))
      (node (ref "L19") (pin "1") (pinfunction "A_1") (pintype "passive"))
      (node (ref "L3") (pin "1") (pinfunction "A_1") (pintype "passive"))
      (node (ref "L35") (pin "1") (pinfunction "A_1") (pintype "passive"))
      (node (ref "L51") (pin "1") (pinfunction "A_1") (pintype "passive"))
      (node (ref "L67") (pin "1") (pinfunction "A_1") (pintype "passive"))
      (node (ref "L83") (pin "1") (pinfunction "A_1") (pintype "passive"))
      (node (ref "L99") (pin "1") (pinfunction "A_1") (pintype "passive"))
    )
    (net (code "4") (name "/A3") (class "Default")
      (node (ref "L100") (pin "1") (pinfunction "A_1") (pintype "passive"))
      (node (ref "L116") (pin "1") (pinfunction "A_1") (pintype "passive"))
      (node (ref "L20") (pin "1") (pinfunction "A_1") (pintype "passive"))
      (node (ref "L36") (pin "1") (pinfunction "A_1") (pintype "passive"))
      (node (ref "L4") (pin "1") (pinfunction "A_1") (pintype "passive"))
      (node (ref "L52") (pin "1") (pinfunction "A_1") (pintype "passive"))
      (node (ref "L68") (pin "1") (pinfunction "A_1") (pintype "passive"))
      (node (ref "L84") (pin "1") (pinfunction "A_1") (pintype "passive"))
    )
    (net (code "5") (name "/A4") (class "Default")
      (node (ref "L101") (pin "1") (pinfunction "A_1") (pintype "passive"))
      (node (ref "L117") (pin "1") (pinfunction "A_1") (pintype "passive"))
      (node (ref "L21") (pin "1") (pinfunction "A_1") (pintype "passive"))
      (node (ref "L37") (pin "1") (pinfunction "A_1") (pintype "passive"))
      (node (ref "L5") (pin "1") (pinfunction "A_1") (pintype "passive"))
      (node (ref "L53") (pin "1") (pinfunction "A_1") (pintype "passive"))
      (node (ref "L69") (pin "1") (pinfunction "A_1") (pintype "passive"))
      (node (ref "L85") (pin "1") (pinfunction "A_1") (pintype "passive"))
    )
    (net (code "6") (name "/A5") (class "Default")
      (node (ref "L102") (pin "1") (pinfunction "A_1") (pintype "passive"))
      (node (ref "L118") (pin "1") (pinfunction "A_1") (pintype "passive"))
      (node (ref "L22") (pin "1") (pinfunction "A_1") (pintype "passive"))
      (node (ref "L38") (pin "1") (pinfunction "A_1") (pintype "passive"))
      (node (ref "L54") (pin "1") (pinfunction "A_1") (pintype "passive"))
      (node (ref "L6") (pin "1") (pinfunction "A_1") (pintype "passive"))
      (node (ref "L70") (pin "1") (pinfunction "A_1") (pintype "passive"))
      (node (ref "L86") (pin "1") (pinfunction "A_1") (pintype "passive"))
    )
    (net (code "7") (name "/A6") (class "Default")
      (node (ref "L103") (pin "1") (pinfunction "A_1") (pintype "passive"))
      (node (ref "L119") (pin "1") (pinfunction "A_1") (pintype "passive"))
      (node (ref "L23") (pin "1") (pinfunction "A_1") (pintype "passive"))
      (node (ref "L39") (pin "1") (pinfunction "A_1") (pintype "passive"))
      (node (ref "L55") (pin "1") (pinfunction "A_1") (pintype "passive"))
      (node (ref "L7") (pin "1") (pinfunction "A_1") (pintype "passive"))
      (node (ref "L71") (pin "1") (pinfunction "A_1") (pintype "passive"))
      (node (ref "L87") (pin "1") (pinfunction "A_1") (pintype "passive"))
    )
    (net (code "8") (name "/A7") (class "Default")
      (node (ref "L104") (pin "1") (pinfunction "A_1") (pintype "passive"))
      (node (ref "L120") (pin "1") (pinfunction "A_1") (pintype "passive"))
      (node (ref "L24") (pin "1") (pinfunction "A_1") (pintype "passive"))
      (node (ref "L40") (pin "1") (pinfunction "A_1") (pintype "passive"))
      (node (ref "L56") (pin "1") (pinfunction "A_1") (pintype "passive"))
      (node (ref "L72") (pin "1") (pinfunction "A_1") (pintype "passive"))
      (node (ref "L8") (pin "1") (pinfunction "A_1") (pintype "passive"))
      (node (ref "L88") (pin "1") (pinfunction "A_1") (pintype "passive"))
    )
    (net (code "9") (name "/A8") (class "Default")
      (node (ref "L105") (pin "1") (pinfunction "A_1") (pintype "passive"))
      (node (ref "L121") (pin "1") (pinfunction "A_1") (pintype "passive"))
      (node (ref "L25") (pin "1") (pinfunction "A_1") (pintype "passive"))
      (node (ref "L41") (pin "1") (pinfunction "A_1") (pintype "passive"))
      (node (ref "L57") (pin "1") (pinfunction "A_1") (pintype "passive"))
      (node (ref "L73") (pin "1") (pinfunction "A_1") (pintype "passive"))
      (node (ref "L89") (pin "1") (pinfunction "A_1") (pintype "passive"))
      (node (ref "L9") (pin "1") (pinfunction "A_1") (pintype "passive"))
    )
    (net (code "10") (name "/A9") (class "Default")
      (node (ref "L10") (pin "1") (pinfunction "A_1") (pintype "passive"))
      (node (ref "L106") (pin "1") (pinfunction "A_1") (pintype "passive"))
      (node (ref "L122") (pin "1") (pinfunction "A_1") (pintype "passive"))
      (node (ref "L26") (pin "1") (pinfunction "A_1") (pintype "passive"))
      (node (ref "L42") (pin "1") (pinfunction "A_1") (pintype "passive"))
      (node (ref "L58") (pin "1") (pinfunction "A_1") (pintype "passive"))
      (node (ref "L74") (pin "1") (pinfunction "A_1") (pintype "passive"))
      (node (ref "L90") (pin "1") (pinfunction "A_1") (pintype "passive"))
    )
    (net (code "11") (name "/A10") (class "Default")
      (node (ref "L107") (pin "1") (pinfunction "A_1") (pintype "passive"))
      (node (ref "L11") (pin "1") (pinfunction "A_1") (pintype "passive"))
      (node (ref "L123") (pin "1") (pinfunction "A_1") (pintype "passive"))
      (node (ref "L27") (pin "1") (pinfunction "A_1") (pintype "passive"))
      (node (ref "L43") (pin "1") (pinfunction "A_1") (pintype "passive"))
      (node (ref "L59") (pin "1") (pinfunction "A_1") (pintype "passive"))
      (node (ref "L75") (pin "1") (pinfunction "A_1") (pintype "passive"))
      (node (ref "L91") (pin "1") (pinfunction "A_1") (pintype "passive"))
    )
    (net (code "12") (name "/A11") (class "Default")
      (node (ref "L108") (pin "1") (pinfunction "A_1") (pintype "passive"))
      (node (ref "L12") (pin "1") (pinfunction "A_1") (pintype "passive"))
      (node (ref "L124") (pin "1") (pinfunction "A_1") (pintype "passive"))
      (node (ref "L28") (pin "1") (pinfunction "A_1") (pintype "passive"))
      (node (ref "L44") (pin "1") (pinfunction "A_1") (pintype "passive"))
      (node (ref "L60") (pin "1") (pinfunction "A_1") (pintype "passive"))
      (node (ref "L76") (pin "1") (pinfunction "A_1") (pintype "passive"))
      (node (ref "L92") (pin "1") (pinfunction "A_1") (pintype "passive"))
    )
    (net (code "13") (name "/A12") (class "Default")
      (node (ref "L109") (pin "1") (pinfunction "A_1") (pintype "passive"))
      (node (ref "L125") (pin "1") (pinfunction "A_1") (pintype "passive"))
      (node (ref "L13") (pin "1") (pinfunction "A_1") (pintype "passive"))
      (node (ref "L29") (pin "1") (pinfunction "A_1") (pintype "passive"))
      (node (ref "L45") (pin "1") (pinfunction "A_1") (pintype "passive"))
      (node (ref "L61") (pin "1") (pinfunction "A_1") (pintype "passive"))
      (node (ref "L77") (pin "1") (pinfunction "A_1") (pintype "passive"))
      (node (ref "L93") (pin "1") (pinfunction "A_1") (pintype "passive"))
    )
    (net (code "14") (name "/A13") (class "Default")
      (node (ref "L110") (pin "1") (pinfunction "A_1") (pintype "passive"))
      (node (ref "L126") (pin "1") (pinfunction "A_1") (pintype "passive"))
      (node (ref "L14") (pin "1") (pinfunction "A_1") (pintype "passive"))
      (node (ref "L30") (pin "1") (pinfunction "A_1") (pintype "passive"))
      (node (ref "L46") (pin "1") (pinfunction "A_1") (pintype "passive"))
      (node (ref "L62") (pin "1") (pinfunction "A_1") (pintype "passive"))
      (node (ref "L78") (pin "1") (pinfunction "A_1") (pintype "passive"))
      (node (ref "L94") (pin "1") (pinfunction "A_1") (pintype "passive"))
    )
    (net (code "15") (name "/A14") (class "Default")
      (node (ref "L111") (pin "1") (pinfunction "A_1") (pintype "passive"))
      (node (ref "L127") (pin "1") (pinfunction "A_1") (pintype "passive"))
      (node (ref "L15") (pin "1") (pinfunction "A_1") (pintype "passive"))
      (node (ref "L31") (pin "1") (pinfunction "A_1") (pintype "passive"))
      (node (ref "L47") (pin "1") (pinfunction "A_1") (pintype "passive"))
      (node (ref "L63") (pin "1") (pinfunction "A_1") (pintype "passive"))
      (node (ref "L79") (pin "1") (pinfunction "A_1") (pintype "passive"))
      (node (ref "L95") (pin "1") (pinfunction "A_1") (pintype "passive"))
    )
    (net (code "16") (name "/A15") (class "Default")
      (node (ref "L112") (pin "1") (pinfunction "A_1") (pintype "passive"))
      (node (ref "L128") (pin "1") (pinfunction "A_1") (pintype "passive"))
      (node (ref "L16") (pin "1") (pinfunction "A_1") (pintype "passive"))
      (node (ref "L32") (pin "1") (pinfunction "A_1") (pintype "passive"))
      (node (ref "L48") (pin "1") (pinfunction "A_1") (pintype "passive"))
      (node (ref "L64") (pin "1") (pinfunction "A_1") (pintype "passive"))
      (node (ref "L80") (pin "1") (pinfunction "A_1") (pintype "passive"))
      (node (ref "L96") (pin "1") (pinfunction "A_1") (pintype "passive"))
    )
    (net (code "19") (name "/C0") (class "Default")
      (node (ref "L1") (pin "2") (pinfunction "K_2") (pintype "passive"))
      (node (ref "L10") (pin "2") (pinfunction "K_2") (pintype "passive"))
      (node (ref "L11") (pin "2") (pinfunction "K_2") (pintype "passive"))
      (node (ref "L12") (pin "2") (pinfunction "K_2") (pintype "passive"))
      (node (ref "L13") (pin "2") (pinfunction "K_2") (pintype "passive"))
      (node (ref "L14") (pin "2") (pinfunction "K_2") (pintype "passive"))
      (node (ref "L15") (pin "2") (pinfunction "K_2") (pintype "passive"))
      (node (ref "L16") (pin "2") (pinfunction "K_2") (pintype "passive"))
      (node (ref "L2") (pin "2") (pinfunction "K_2") (pintype "passive"))
      (node (ref "L3") (pin "2") (pinfunction "K_2") (pintype "passive"))
      (node (ref "L4") (pin "2") (pinfunction "K_2") (pintype "passive"))
      (node (ref "L5") (pin "2") (pinfunction "K_2") (pintype "passive"))
      (node (ref "L6") (pin "2") (pinfunction "K_2") (pintype "passive"))
      (node (ref "L7") (pin "2") (pinfunction "K_2") (pintype "passive"))
      (node (ref "L8") (pin "2") (pinfunction "K_2") (pintype "passive"))
      (node (ref "L9") (pin "2") (pinfunction "K_2") (pintype "passive"))
    )
    (net (code "20") (name "/C1") (class "Default")
      (node (ref "L17") (pin "2") (pinfunction "K_2") (pintype "passive"))
      (node (ref "L18") (pin "2") (pinfunction "K_2") (pintype "passive"))
      (node (ref "L19") (pin "2") (pinfunction "K_2") (pintype "passive"))
      (node (ref "L20") (pin "2") (pinfunction "K_2") (pintype "passive"))
      (node (ref "L21") (pin "2") (pinfunction "K_2") (pintype "passive"))
      (node (ref "L22") (pin "2") (pinfunction "K_2") (pintype "passive"))
      (node (ref "L23") (pin "2") (pinfunction "K_2") (pintype "passive"))
      (node (ref "L24") (pin "2") (pinfunction "K_2") (pintype "passive"))
      (node (ref "L25") (pin "2") (pinfunction "K_2") (pintype "passive"))
      (node (ref "L26") (pin "2") (pinfunction "K_2") (pintype "passive"))
      (node (ref "L27") (pin "2") (pinfunction "K_2") (pintype "passive"))
      (node (ref "L28") (pin "2") (pinfunction "K_2") (pintype "passive"))
      (node (ref "L29") (pin "2") (pinfunction "K_2") (pintype "passive"))
      (node (ref "L30") (pin "2") (pinfunction "K_2") (pintype "passive"))
      (node (ref "L31") (pin "2") (pinfunction "K_2") (pintype "passive"))
      (node (ref "L32") (pin "2") (pinfunction "K_2") (pintype "passive"))
    )
    (net (code "21") (name "/C2") (class "Default")
      (node (ref "L33") (pin "2") (pinfunction "K_2") (pintype "passive"))
      (node (ref "L34") (pin "2") (pinfunction "K_2") (pintype "passive"))
      (node (ref "L35") (pin "2") (pinfunction "K_2") (pintype "passive"))
      (node (ref "L36") (pin "2") (pinfunction "K_2") (pintype "passive"))
      (node (ref "L37") (pin "2") (pinfunction "K_2") (pintype "passive"))
      (node (ref "L38") (pin "2") (pinfunction "K_2") (pintype "passive"))
      (node (ref "L39") (pin "2") (pinfunction "K_2") (pintype "passive"))
      (node (ref "L40") (pin "2") (pinfunction "K_2") (pintype "passive"))
      (node (ref "L41") (pin "2") (pinfunction "K_2") (pintype "passive"))
      (node (ref "L42") (pin "2") (pinfunction "K_2") (pintype "passive"))
      (node (ref "L43") (pin "2") (pinfunction "K_2") (pintype "passive"))
      (node (ref "L44") (pin "2") (pinfunction "K_2") (pintype "passive"))
      (node (ref "L45") (pin "2") (pinfunction "K_2") (pintype "passive"))
      (node (ref "L46") (pin "2") (pinfunction "K_2") (pintype "passive"))
      (node (ref "L47") (pin "2") (pinfunction "K_2") (pintype "passive"))
      (node (ref "L48") (pin "2") (pinfunction "K_2") (pintype "passive"))
    )
    (net (code "22") (name "/C3") (class "Default")
      (node (ref "L49") (pin "2") (pinfunction "K_2") (pintype "passive"))
      (node (ref "L50") (pin "2") (pinfunction "K_2") (pintype "passive"))
      (node (ref "L51") (pin "2") (pinfunction "K_2") (pintype "passive"))
      (node (ref "L52") (pin "2") (pinfunction "K_2") (pintype "passive"))
      (node (ref "L53") (pin "2") (pinfunction "K_2") (pintype "passive"))
      (node (ref "L54") (pin "2") (pinfunction "K_2") (pintype "passive"))
      (node (ref "L55") (pin "2") (pinfunction "K_2") (pintype "passive"))
      (node (ref "L56") (pin "2") (pinfunction "K_2") (pintype "passive"))
      (node (ref "L57") (pin "2") (pinfunction "K_2") (pintype "passive"))
      (node (ref "L58") (pin "2") (pinfunction "K_2") (pintype "passive"))
      (node (ref "L59") (pin "2") (pinfunction "K_2") (pintype "passive"))
      (node (ref "L60") (pin "2") (pinfunction "K_2") (pintype "passive"))
      (node (ref "L61") (pin "2") (pinfunction "K_2") (pintype "passive"))
      (node (ref "L62") (pin "2") (pinfunction "K_2") (pintype "passive"))
      (node (ref "L63") (pin "2") (pinfunction "K_2") (pintype "passive"))
      (node (ref "L64") (pin "2") (pinfunction "K_2") (pintype "passive"))
    )
    (net (code "23") (name "/C4") (class "Default")
      (node (ref "L65") (pin "2") (pinfunction "K_2") (pintype "passive"))
      (node (ref "L66") (pin "2") (pinfunction "K_2") (pintype "passive"))
      (node (ref "L67") (pin "2") (pinfunction "K_2") (pintype "passive"))
      (node (ref "L68") (pin "2") (pinfunction "K_2") (pintype "passive"))
      (node (ref "L69") (pin "2") (pinfunction "K_2") (pintype "passive"))
      (node (ref "L70") (pin "2") (pinfunction "K_2") (pintype "passive"))
      (node (ref "L71") (pin "2") (pinfunction "K_2") (pintype "passive"))
      (node (ref "L72") (pin "2") (pinfunction "K_2") (pintype "passive"))
      (node (ref "L73") (pin "2") (pinfunction "K_2") (pintype "passive"))
      (node (ref "L74") (pin "2") (pinfunction "K_2") (pintype "passive"))
      (node (ref "L75") (pin "2") (pinfunction "K_2") (pintype "passive"))
      (node (ref "L76") (pin "2") (pinfunction "K_2") (pintype "passive"))
      (node (ref "L77") (pin "2") (pinfunction "K_2") (pintype "passive"))
      (node (ref "L78") (pin "2") (pinfunction "K_2") (pintype "passive"))
      (node (ref "L79") (pin "2") (pinfunction "K_2") (pintype "passive"))
      (node (ref "L80") (pin "2") (pinfunction "K_2") (pintype "passive"))
    )
    (net (code "24") (name "/C5") (class "Default")
      (node (ref "L81") (pin "2") (pinfunction "K_2") (pintype "passive"))
      (node (ref "L82") (pin "2") (pinfunction "K_2") (pintype "passive"))
      (node (ref "L83") (pin "2") (pinfunction "K_2") (pintype "passive"))
      (node (ref "L84") (pin "2") (pinfunction "K_2") (pintype "passive"))
      (node (ref "L85") (pin "2") (pinfunction "K_2") (pintype "passive"))
      (node (ref "L86") (pin "2") (pinfunction "K_2") (pintype "passive"))
      (node (ref "L87") (pin "2") (pinfunction "K_2") (pintype "passive"))
      (node (ref "L88") (pin "2") (pinfunction "K_2") (pintype "passive"))
      (node (ref "L89") (pin "2") (pinfunction "K_2") (pintype "passive"))
      (node (ref "L90") (pin "2") (pinfunction "K_2") (pintype "passive"))
      (node (ref "L91") (pin "2") (pinfunction "K_2") (pintype "passive"))
      (node (ref "L92") (pin "2") (pinfunction "K_2") (pintype "passive"))
      (node (ref "L93") (pin "2") (pinfunction "K_2") (pintype "passive"))
      (node (ref "L94") (pin "2") (pinfunction "K_2") (pintype "passive"))
      (node (ref "L95") (pin "2") (pinfunction "K_2") (pintype "passive"))
      (node (ref "L96") (pin "2") (pinfunction "K_2") (pintype "passive"))
    )
    (net (code "25") (name "/C6") (class "Default")
      (node (ref "L100") (pin "2") (pinfunction "K_2") (pintype "passive"))
      (node (ref "L101") (pin "2") (pinfunction "K_2") (pintype "passive"))
      (node (ref "L102") (pin "2") (pinfunction "K_2") (pintype "passive"))
      (node (ref "L103") (pin "2") (pinfunction "K_2") (pintype "passive"))
      (node (ref "L104") (pin "2") (pinfunction "K_2") (pintype "passive"))
      (node (ref "L105") (pin "2") (pinfunction "K_2") (pintype "passive"))
      (node (ref "L106") (pin "2") (pinfunction "K_2") (pintype "passive"))
      (node (ref "L107") (pin "2") (pinfunction "K_2") (pintype "passive"))
      (node (ref "L108") (pin "2") (pinfunction "K_2") (pintype "passive"))
      (node (ref "L109") (pin "2") (pinfunction "K_2") (pintype "passive"))
      (node (ref "L110") (pin "2") (pinfunction "K_2") (pintype "passive"))
      (node (ref "L111") (pin "2") (pinfunction "K_2") (pintype "passive"))
      (node (ref "L112") (pin "2") (pinfunction "K_2") (pintype "passive"))
      (node (ref "L97") (pin "2") (pinfunction "K_2") (pintype "passive"))
      (node (ref "L98") (pin "2") (pinfunction "K_2") (pintype "passive"))
      (node (ref "L99") (pin "2") (pinfunction "K_2") (pintype "passive"))
    )
    (net (code "26") (name "/C7") (class "Default")
      (node (ref "L113") (pin "2") (pinfunction "K_2") (pintype "passive"))
      (node (ref "L114") (pin "2") (pinfunction "K_2") (pintype "passive"))
      (node (ref "L115") (pin "2") (pinfunction "K_2") (pintype "passive"))
      (node (ref "L116") (pin "2") (pinfunction "K_2") (pintype "passive"))
      (node (ref "L117") (pin "2") (pinfunction "K_2") (pintype "passive"))
      (node (ref "L118") (pin "2") (pinfunction "K_2") (pintype "passive"))
      (node (ref "L119") (pin "2") (pinfunction "K_2") (pintype "passive"))
      (node (ref "L120") (pin "2") (pinfunction "K_2") (pintype "passive"))
      (node (ref "L121") (pin "2") (pinfunction "K_2") (pintype "passive"))
      (node (ref "L122") (pin "2") (pinfunction "K_2") (pintype "passive"))
      (node (ref "L123") (pin "2") (pinfunction "K_2") (pintype "passive"))
      (node (ref "L124") (pin "2") (pinfunction "K_2") (pintype "passive"))
      (node (ref "L125") (pin "2") (pinfunction "K_2") (pintype "passive"))
      (node (ref "L126") (pin "2") (pinfunction "K_2") (pintype "passive"))
      (node (ref "L127") (pin "2") (pinfunction "K_2") (pintype "passive"))
      (node (ref "L128") (pin "2") (pinfunction "K_2") (pintype "passive"))
    )
  )
)
